# M6_base_simple.net
KiCad netlist of a schematic drawn in Altium Designer
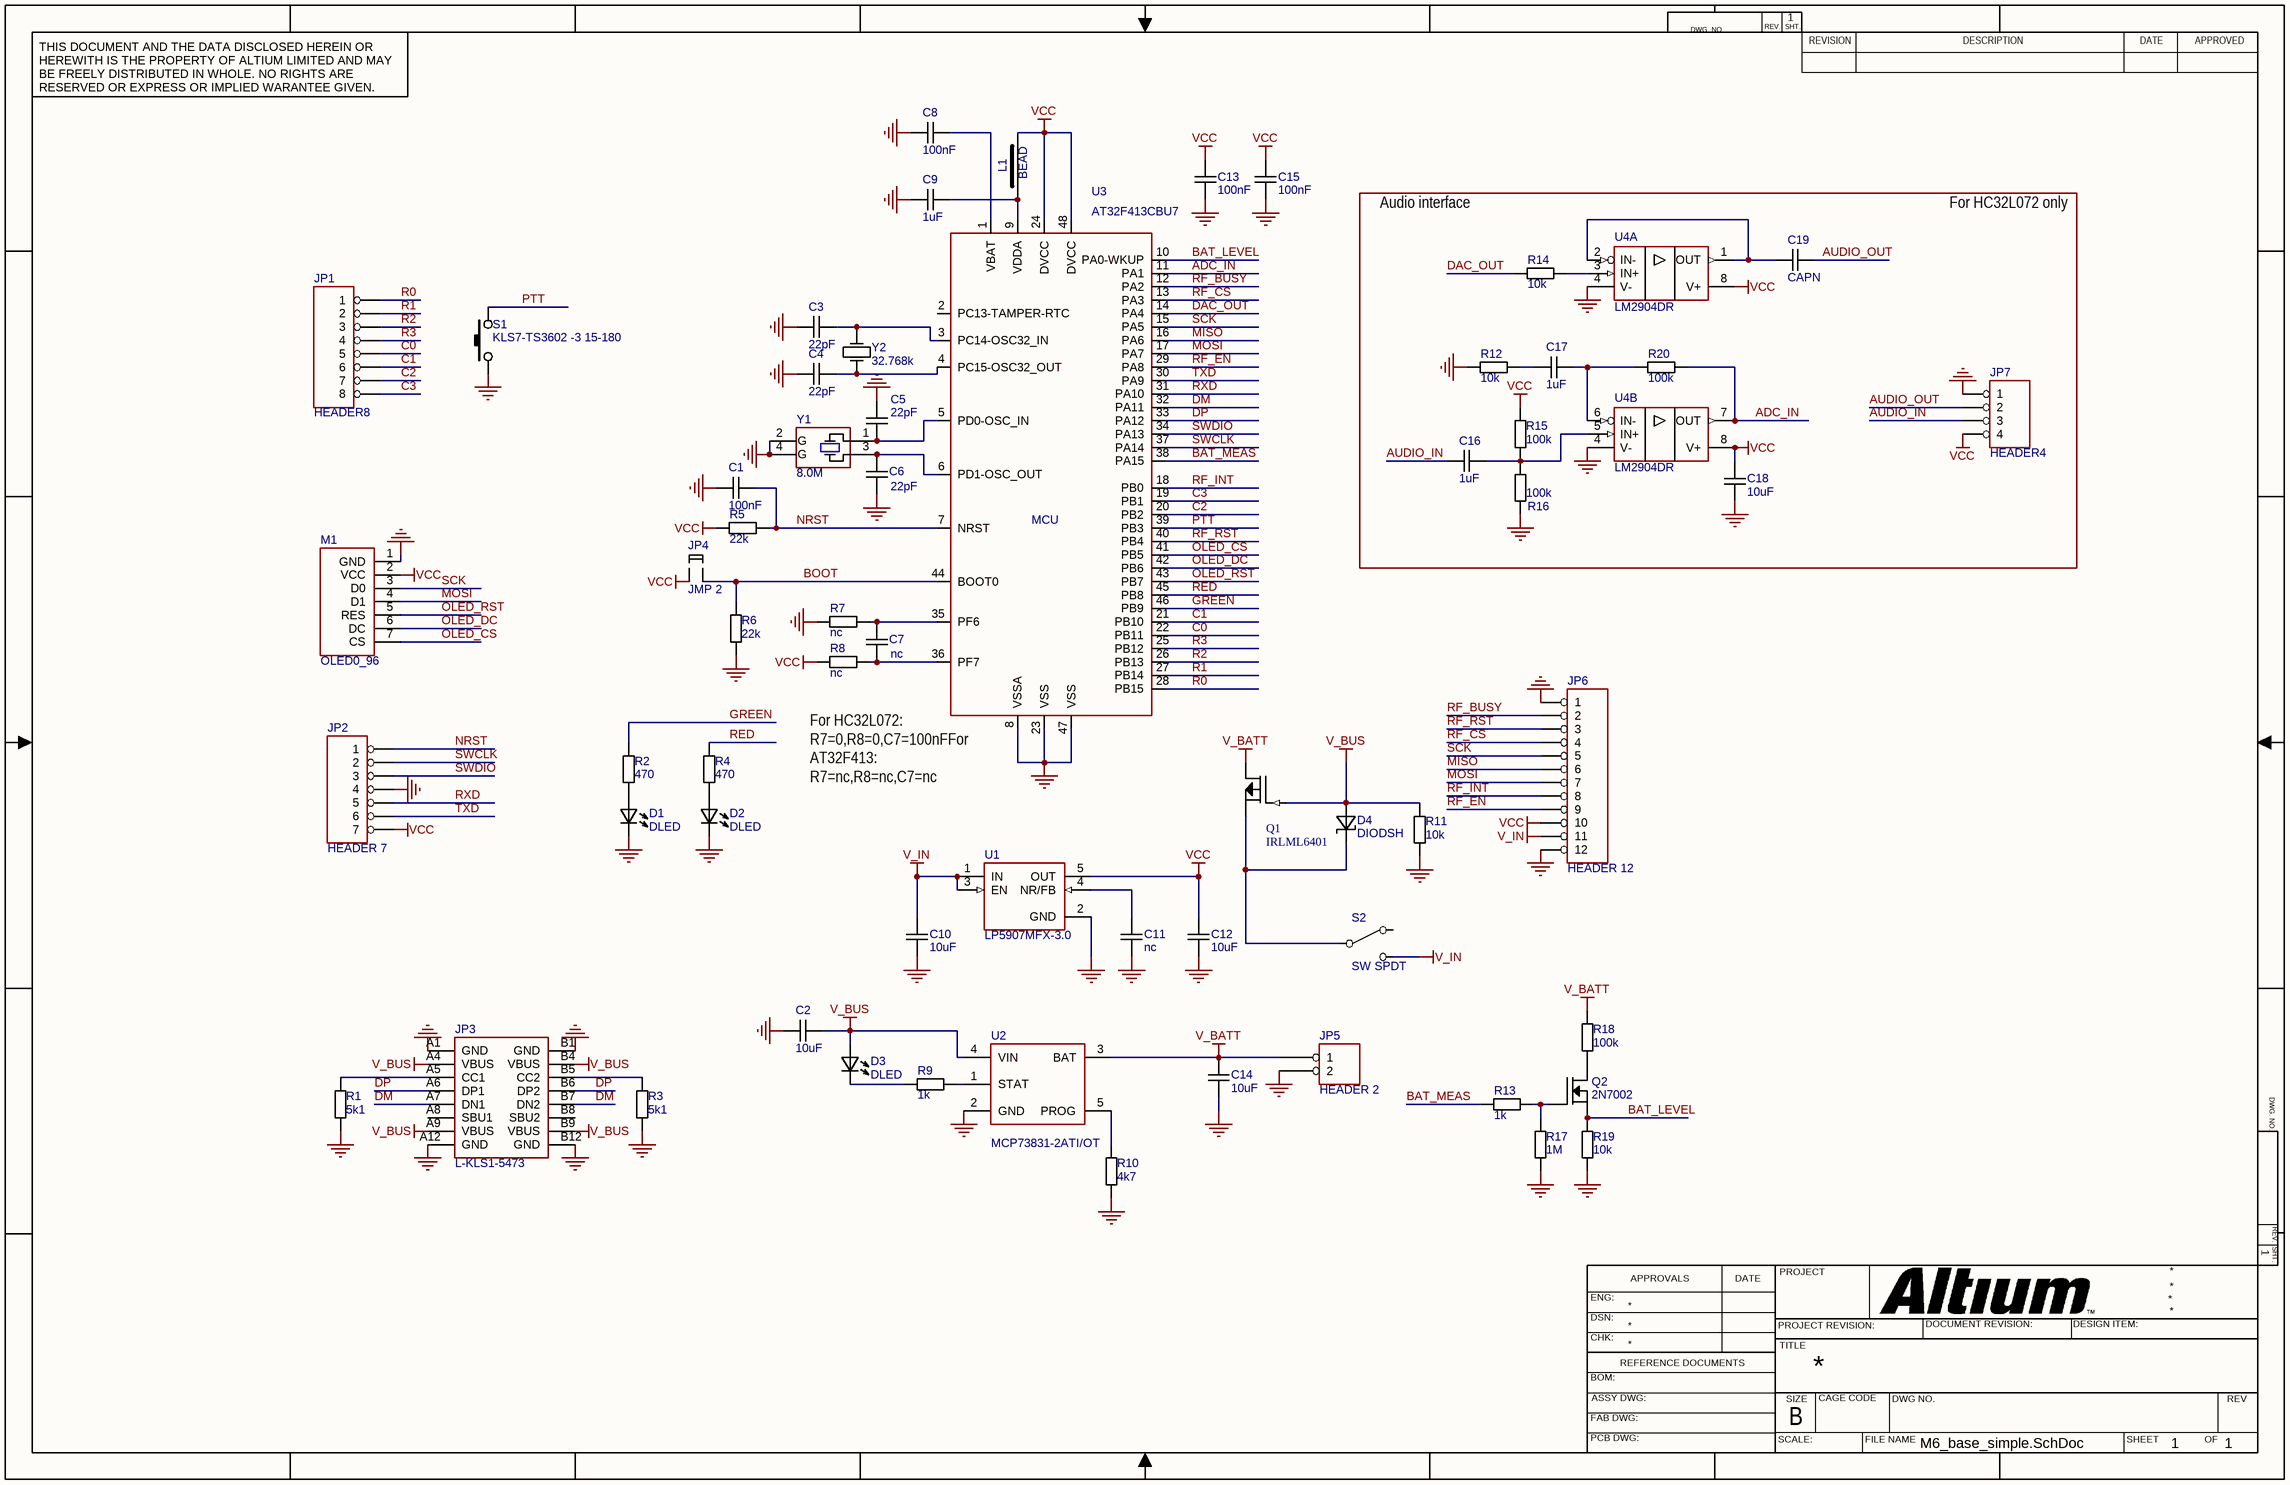
[diagram p0: M6_base_simple.SchDoc]

(export (version "E")
  (design (tool "Eeschema 10.0.6"))
  (components
    (comp (ref "C1")
      (value "100nF")
      (footprint "C-0603")
      (fields (field (name "VOLTAGE") "50V"))
      (libsource (lib "Passive") (part "CAPN"))
    )
    (comp (ref "C2")
      (value "10uF")
      (footprint "C-0805")
      (fields (field (name "VOLTAGE") "50V"))
      (libsource (lib "Passive") (part "CAPN"))
    )
    (comp (ref "C3")
      (value "22pF")
      (footprint "C-0603")
      (fields (field (name "VOLTAGE") "50V"))
      (libsource (lib "Passive") (part "CAPN"))
    )
    (comp (ref "C4")
      (value "22pF")
      (footprint "C-0603")
      (fields (field (name "VOLTAGE") "50V"))
      (libsource (lib "Passive") (part "CAPN"))
    )
    (comp (ref "C5")
      (value "22pF")
      (footprint "C-0603")
      (fields (field (name "VOLTAGE") "50V"))
      (libsource (lib "Passive") (part "CAPN"))
    )
    (comp (ref "C6")
      (value "22pF")
      (footprint "C-0603")
      (fields (field (name "VOLTAGE") "50V"))
      (libsource (lib "Passive") (part "CAPN"))
    )
    (comp (ref "C7")
      (value "nc")
      (footprint "C-0603")
      (fields (field (name "VOLTAGE") "50V"))
      (libsource (lib "Passive") (part "CAPN"))
    )
    (comp (ref "C8")
      (value "100nF")
      (footprint "C-0603")
      (fields (field (name "VOLTAGE") "50V"))
      (libsource (lib "Passive") (part "CAPN"))
    )
    (comp (ref "C9")
      (value "1uF")
      (footprint "C-0603")
      (fields (field (name "VOLTAGE") "50V"))
      (libsource (lib "Passive") (part "CAPN"))
    )
    (comp (ref "C10")
      (value "10uF")
      (footprint "C-0805")
      (fields (field (name "VOLTAGE") "50V"))
      (libsource (lib "Passive") (part "CAPN"))
    )
    (comp (ref "C11")
      (value "nc")
      (footprint "C-0603")
      (fields (field (name "VOLTAGE") "50V"))
      (libsource (lib "Passive") (part "CAPN"))
    )
    (comp (ref "C12")
      (value "10uF")
      (footprint "C-0805")
      (fields (field (name "VOLTAGE") "50V"))
      (libsource (lib "Passive") (part "CAPN"))
    )
    (comp (ref "C13")
      (value "100nF")
      (footprint "C-0603")
      (fields (field (name "VOLTAGE") "50V"))
      (libsource (lib "Passive") (part "CAPN"))
    )
    (comp (ref "C14")
      (value "10uF")
      (footprint "C-0805")
      (fields (field (name "VOLTAGE") "50V"))
      (libsource (lib "Passive") (part "CAPN"))
    )
    (comp (ref "C15")
      (value "100nF")
      (footprint "C-0603")
      (fields (field (name "VOLTAGE") "50V"))
      (libsource (lib "Passive") (part "CAPN"))
    )
    (comp (ref "C16")
      (value "1uF")
      (footprint "C-0603")
      (fields (field (name "VOLTAGE") "50V"))
      (libsource (lib "Passive") (part "CAPN"))
    )
    (comp (ref "C17")
      (value "1uF")
      (footprint "C-0603")
      (fields (field (name "VOLTAGE") "50V"))
      (libsource (lib "Passive") (part "CAPN"))
    )
    (comp (ref "C18")
      (value "10uF")
      (footprint "C-0805")
      (fields (field (name "VOLTAGE") "50V"))
      (libsource (lib "Passive") (part "CAPN"))
    )
    (comp (ref "C19")
      (value "CAPN")
      (footprint "C-0805")
      (fields (field (name "VOLTAGE") "50V"))
      (libsource (lib "Passive") (part "CAPN"))
    )
    (comp (ref "D1") (value "DLED") (footprint "LED_3mm_RED") (libsource (lib "Diodes") (part "DLED")))
    (comp (ref "D2") (value "DLED") (footprint "LED_3mm_RED") (libsource (lib "Diodes") (part "DLED")))
    (comp (ref "D3") (value "DLED") (footprint "LED_3mm_RED") (libsource (lib "Diodes") (part "DLED")))
    (comp (ref "D4") (value "DIODSH") (footprint "D-SMA") (libsource (lib "Diodes") (part "DIODSH")))
    (comp (ref "JP1")
      (value "HEADER8")
      (footprint "PLS1-8R_1")
      (libsource (lib "Connectors") (part "HEADER8"))
    )
    (comp (ref "JP2")
      (value "HEADER 7")
      (footprint "PLS1-7")
      (libsource (lib "Connectors") (part "HEADER 7"))
    )
    (comp (ref "JP3")
      (value "L-KLS1-5473")
      (footprint "L-KLS1-5473")
      (libsource (lib "Connectors") (part "L-KLS1-5473"))
    )
    (comp (ref "JP4") (value "JMP 2") (footprint "PLS1-2") (libsource (lib "Connectors") (part "JMP 2")))
    (comp (ref "JP5")
      (value "HEADER 2")
      (footprint "PLS1-2")
      (libsource (lib "Connectors") (part "HEADER 2"))
    )
    (comp (ref "JP6")
      (value "HEADER 12")
      (footprint "PLS1-12R_1")
      (libsource (lib "Connectors") (part "HEADER 12"))
    )
    (comp (ref "JP7") (value "HEADER4") (footprint "PLS1-4R") (libsource (lib "Connectors") (part "HEADER4")))
    (comp (ref "L1") (value "BEAD") (footprint "L-0603") (libsource (lib "Passive") (part "BEAD")))
    (comp (ref "M1") (value "OLED0_96") (footprint "OLED096") (libsource (lib "RFmodules") (part "OLED0_96")))
    (comp (ref "Q1") (value "IRLML6401") (footprint "SOT-23") (libsource (lib "Discrete") (part "MOSF-P")))
    (comp (ref "Q2") (value "2N7002") (footprint "SOT-23") (libsource (lib "Transistors") (part "MOSF-N")))
    (comp (ref "R1") (value "5k1") (footprint "R-0603") (libsource (lib "Passive") (part "RES")))
    (comp (ref "R2") (value "470") (footprint "R-0603") (libsource (lib "Passive") (part "RES")))
    (comp (ref "R3") (value "5k1") (footprint "R-0603") (libsource (lib "Passive") (part "RES")))
    (comp (ref "R4") (value "470") (footprint "R-0603") (libsource (lib "Passive") (part "RES")))
    (comp (ref "R5") (value "22k") (footprint "R-0603") (libsource (lib "") (part "RES_1")))
    (comp (ref "R6") (value "22k") (footprint "R-0603") (libsource (lib "Passive") (part "RES")))
    (comp (ref "R7") (value "nc") (footprint "R-0603") (libsource (lib "") (part "RES_1")))
    (comp (ref "R8") (value "nc") (footprint "R-0603") (libsource (lib "") (part "RES_1")))
    (comp (ref "R9") (value "1k") (footprint "R-0603") (libsource (lib "") (part "RES_2")))
    (comp (ref "R10") (value "4k7") (footprint "R-0603") (libsource (lib "Passive") (part "RES")))
    (comp (ref "R11") (value "10k") (footprint "R-0603") (libsource (lib "Passive") (part "RES")))
    (comp (ref "R12") (value "10k") (footprint "R-0603") (libsource (lib "") (part "RES_1")))
    (comp (ref "R13") (value "1k") (footprint "R-0603") (libsource (lib "") (part "RES_2")))
    (comp (ref "R14") (value "10k") (footprint "R-0603") (libsource (lib "") (part "RES_1")))
    (comp (ref "R15") (value "100k") (footprint "R-0603") (libsource (lib "Passive") (part "RES")))
    (comp (ref "R16") (value "100k") (footprint "R-0603") (libsource (lib "") (part "RES_3")))
    (comp (ref "R17") (value "1M") (footprint "R-0603") (libsource (lib "Passive") (part "RES")))
    (comp (ref "R18") (value "100k") (footprint "R-0603") (libsource (lib "Passive") (part "RES")))
    (comp (ref "R19") (value "10k") (footprint "R-0603") (libsource (lib "Passive") (part "RES")))
    (comp (ref "R20") (value "100k") (footprint "R-0603") (libsource (lib "") (part "RES_2")))
    (comp (ref "S1")
      (value "KLS7-TS3602 -3 15-180")
      (footprint "KLS7-TS3602")
      (libsource (lib "Switches") (part "SW-1"))
    )
    (comp (ref "S2")
      (value "SW SPDT")
      (footprint "SK-12D07VG5")
      (libsource (lib "Switches") (part "SW SPDT"))
    )
    (comp (ref "U1")
      (value "LP5907MFX-3.0")
      (footprint "SOT-23-5")
      (description "250mA Low-Dropout Regulator")
      (libsource (lib "ICs") (part "LP5907"))
    )
    (comp (ref "U2")
      (value "MCP73831-2ATI/OT")
      (footprint "SOT-23-5")
      (fields
        (field (name "LIBRARY PART") "IC`s.SchLib")
        (field (name "FOOTPRINT PART") "IC-package.PcbLib")
        (field (name "MANUFACTURER") "Texas Instruments")
      )
      (libsource (lib "ICs") (part "MCP73831-2ATI/OT"))
    )
    (comp (ref "U3")
      (value "AT32F413CBU7")
      (footprint "LQFP-48")
      (libsource (lib "MCUs") (part "AT32F413CBU7"))
    )
    (comp (ref "U4")
      (value "LM2904DR")
      (footprint "SO-8")
      (description "Dual Operational Amplifiers, SOIC-8")
      (libsource (lib "ICs") (part "LM2904"))
    )
    (comp (ref "Y1")
      (value "8.0M")
      (footprint "ZQ_SJK-7U")
      (description "Crystal, 24 MHz, 9 pF, SMD")
      (libsource (lib "Passive") (part "TSX-3225"))
    )
    (comp (ref "Y2") (value "32.768k") (footprint "KX-327") (libsource (lib "Passive") (part "Y")))
  )
  (nets
    (net (code "1") (name "/ADC_IN") (class "Default")
      (node (ref "R20") (pin "1") (pinfunction "1_1") (pintype "passive"))
      (node (ref "U3") (pin "11") (pinfunction "PA1_11") (pintype "passive"))
      (node (ref "U4") (pin "7") (pinfunction "OUT_7") (pintype "output"))
    )
    (net (code "2") (name "/AUDIO_IN") (class "Default")
      (node (ref "C16") (pin "1") (pinfunction "1_1") (pintype "passive"))
      (node (ref "JP7") (pin "3") (pinfunction "3_3") (pintype "passive"))
    )
    (net (code "3") (name "/AUDIO_OUT") (class "Default")
      (node (ref "C19") (pin "2") (pinfunction "2_2") (pintype "passive"))
      (node (ref "JP7") (pin "2") (pinfunction "2_2") (pintype "passive"))
    )
    (net (code "4") (name "/BAT_LEVEL") (class "Default")
      (node (ref "Q2") (pin "2") (pinfunction "SOURCE_2") (pintype "passive"))
      (node (ref "R19") (pin "2") (pinfunction "2_2") (pintype "passive"))
      (node (ref "U3") (pin "10") (pinfunction "PA0-WKUP_10") (pintype "passive"))
    )
    (net (code "5") (name "/BAT_MEAS") (class "Default")
      (node (ref "R13") (pin "2") (pinfunction "2_2") (pintype "passive"))
      (node (ref "U3") (pin "38") (pinfunction "PA15_38") (pintype "passive"))
    )
    (net (code "6") (name "/BOOT") (class "Default")
      (node (ref "JP4") (pin "2") (pinfunction "2_2") (pintype "passive"))
      (node (ref "R6") (pin "2") (pinfunction "2_2") (pintype "passive"))
      (node (ref "U3") (pin "44") (pinfunction "BOOT0_44") (pintype "passive"))
    )
    (net (code "7") (name "/C0") (class "Default")
      (node (ref "JP1") (pin "5") (pinfunction "5_5") (pintype "passive"))
      (node (ref "U3") (pin "22") (pinfunction "PB11_22") (pintype "passive"))
    )
    (net (code "8") (name "/C1") (class "Default")
      (node (ref "JP1") (pin "6") (pinfunction "6_6") (pintype "passive"))
      (node (ref "U3") (pin "21") (pinfunction "PB10_21") (pintype "passive"))
    )
    (net (code "9") (name "/C2") (class "Default")
      (node (ref "JP1") (pin "7") (pinfunction "7_7") (pintype "passive"))
      (node (ref "U3") (pin "20") (pinfunction "PB2_20") (pintype "passive"))
    )
    (net (code "10") (name "/C3") (class "Default")
      (node (ref "JP1") (pin "8") (pinfunction "8_8") (pintype "passive"))
      (node (ref "U3") (pin "19") (pinfunction "PB1_19") (pintype "passive"))
    )
    (net (code "11") (name "/DAC_OUT") (class "Default")
      (node (ref "R14") (pin "1") (pinfunction "1_1") (pintype "passive"))
      (node (ref "U3") (pin "14") (pinfunction "PA4_14") (pintype "passive"))
    )
    (net (code "12") (name "/DM") (class "Default")
      (node (ref "JP3") (pin "A7") (pinfunction "DN1_A7") (pintype "passive"))
      (node (ref "JP3") (pin "B7") (pinfunction "DN2_B7") (pintype "passive"))
      (node (ref "U3") (pin "32") (pinfunction "PA11_32") (pintype "passive"))
    )
    (net (code "13") (name "/DP") (class "Default")
      (node (ref "JP3") (pin "A6") (pinfunction "DP1_A6") (pintype "passive"))
      (node (ref "JP3") (pin "B6") (pinfunction "DP2_B6") (pintype "passive"))
      (node (ref "U3") (pin "33") (pinfunction "PA12_33") (pintype "passive"))
    )
    (net (code "14") (name "/GREEN") (class "Default")
      (node (ref "R2") (pin "2") (pinfunction "2_2") (pintype "passive"))
      (node (ref "U3") (pin "46") (pinfunction "PB9_46") (pintype "passive"))
    )
    (net (code "15") (name "/MISO") (class "Default")
      (node (ref "JP6") (pin "6") (pinfunction "6_6") (pintype "passive"))
      (node (ref "U3") (pin "16") (pinfunction "PA6_16") (pintype "passive"))
    )
    (net (code "16") (name "/MOSI") (class "Default")
      (node (ref "JP6") (pin "7") (pinfunction "7_7") (pintype "passive"))
      (node (ref "M1") (pin "4") (pinfunction "D1_4") (pintype "passive"))
      (node (ref "U3") (pin "17") (pinfunction "PA7_17") (pintype "passive"))
    )
    (net (code "17") (name "/NRST") (class "Default")
      (node (ref "C1") (pin "2") (pinfunction "2_2") (pintype "passive"))
      (node (ref "JP2") (pin "1") (pinfunction "1_1") (pintype "passive"))
      (node (ref "R5") (pin "2") (pinfunction "2_2") (pintype "passive"))
      (node (ref "U3") (pin "7") (pinfunction "NRST_7") (pintype "passive"))
    )
    (net (code "18") (name "/OLED_CS") (class "Default")
      (node (ref "M1") (pin "7") (pinfunction "CS_7") (pintype "passive"))
      (node (ref "U3") (pin "41") (pinfunction "PB5_41") (pintype "passive"))
    )
    (net (code "19") (name "/OLED_DC") (class "Default")
      (node (ref "M1") (pin "6") (pinfunction "DC_6") (pintype "passive"))
      (node (ref "U3") (pin "42") (pinfunction "PB6_42") (pintype "passive"))
    )
    (net (code "20") (name "/OLED_RST") (class "Default")
      (node (ref "M1") (pin "5") (pinfunction "RES_5") (pintype "passive"))
      (node (ref "U3") (pin "43") (pinfunction "PB7_43") (pintype "passive"))
    )
    (net (code "21") (name "/PTT") (class "Default")
      (node (ref "S1") (pin "2") (pinfunction "2_2") (pintype "passive"))
      (node (ref "U3") (pin "39") (pinfunction "PB3_39") (pintype "passive"))
    )
    (net (code "22") (name "/R0") (class "Default")
      (node (ref "JP1") (pin "1") (pinfunction "1_1") (pintype "passive"))
      (node (ref "U3") (pin "28") (pinfunction "PB15_28") (pintype "passive"))
    )
    (net (code "23") (name "/R1") (class "Default")
      (node (ref "JP1") (pin "2") (pinfunction "2_2") (pintype "passive"))
      (node (ref "U3") (pin "27") (pinfunction "PB14_27") (pintype "passive"))
    )
    (net (code "24") (name "/R2") (class "Default")
      (node (ref "JP1") (pin "3") (pinfunction "3_3") (pintype "passive"))
      (node (ref "U3") (pin "26") (pinfunction "PB13_26") (pintype "passive"))
    )
    (net (code "25") (name "/R3") (class "Default")
      (node (ref "JP1") (pin "4") (pinfunction "4_4") (pintype "passive"))
      (node (ref "U3") (pin "25") (pinfunction "PB12_25") (pintype "passive"))
    )
    (net (code "26") (name "/RED") (class "Default")
      (node (ref "R4") (pin "2") (pinfunction "2_2") (pintype "passive"))
      (node (ref "U3") (pin "45") (pinfunction "PB8_45") (pintype "passive"))
    )
    (net (code "27") (name "/RF_BUSY") (class "Default")
      (node (ref "JP6") (pin "2") (pinfunction "2_2") (pintype "passive"))
      (node (ref "U3") (pin "12") (pinfunction "PA2_12") (pintype "passive"))
    )
    (net (code "28") (name "/RF_CS") (class "Default")
      (node (ref "JP6") (pin "4") (pinfunction "4_4") (pintype "passive"))
      (node (ref "U3") (pin "13") (pinfunction "PA3_13") (pintype "passive"))
    )
    (net (code "29") (name "/RF_EN") (class "Default")
      (node (ref "JP6") (pin "9") (pinfunction "9_9") (pintype "passive"))
      (node (ref "U3") (pin "29") (pinfunction "PA8_29") (pintype "passive"))
    )
    (net (code "30") (name "/RF_INT") (class "Default")
      (node (ref "JP6") (pin "8") (pinfunction "8_8") (pintype "passive"))
      (node (ref "U3") (pin "18") (pinfunction "PB0_18") (pintype "passive"))
    )
    (net (code "31") (name "/RF_RST") (class "Default")
      (node (ref "JP6") (pin "3") (pinfunction "3_3") (pintype "passive"))
      (node (ref "U3") (pin "40") (pinfunction "PB4_40") (pintype "passive"))
    )
    (net (code "32") (name "/RXD") (class "Default")
      (node (ref "JP2") (pin "5") (pinfunction "5_5") (pintype "passive"))
      (node (ref "U3") (pin "31") (pinfunction "PA10_31") (pintype "passive"))
    )
    (net (code "33") (name "/SCK") (class "Default")
      (node (ref "JP6") (pin "5") (pinfunction "5_5") (pintype "passive"))
      (node (ref "M1") (pin "3") (pinfunction "D0_3") (pintype "passive"))
      (node (ref "U3") (pin "15") (pinfunction "PA5_15") (pintype "passive"))
    )
    (net (code "34") (name "/SWCLK") (class "Default")
      (node (ref "JP2") (pin "2") (pinfunction "2_2") (pintype "passive"))
      (node (ref "U3") (pin "37") (pinfunction "PA14_37") (pintype "passive"))
    )
    (net (code "35") (name "/SWDIO") (class "Default")
      (node (ref "JP2") (pin "3") (pinfunction "3_3") (pintype "passive"))
      (node (ref "U3") (pin "34") (pinfunction "PA13_34") (pintype "passive"))
    )
    (net (code "36") (name "/TXD") (class "Default")
      (node (ref "JP2") (pin "6") (pinfunction "6_6") (pintype "passive"))
      (node (ref "U3") (pin "30") (pinfunction "PA9_30") (pintype "passive"))
    )
    (net (code "37") (name "GND") (class "Default")
      (node (ref "C1") (pin "1") (pinfunction "1_1") (pintype "passive"))
      (node (ref "C10") (pin "2") (pinfunction "2_2") (pintype "passive"))
      (node (ref "C11") (pin "2") (pinfunction "2_2") (pintype "passive"))
      (node (ref "C12") (pin "2") (pinfunction "2_2") (pintype "passive"))
      (node (ref "C13") (pin "1") (pinfunction "1_1") (pintype "passive"))
      (node (ref "C14") (pin "1") (pinfunction "1_1") (pintype "passive"))
      (node (ref "C15") (pin "1") (pinfunction "1_1") (pintype "passive"))
      (node (ref "C18") (pin "1") (pinfunction "1_1") (pintype "passive"))
      (node (ref "C2") (pin "1") (pinfunction "1_1") (pintype "passive"))
      (node (ref "C3") (pin "1") (pinfunction "1_1") (pintype "passive"))
      (node (ref "C4") (pin "1") (pinfunction "1_1") (pintype "passive"))
      (node (ref "C5") (pin "1") (pinfunction "1_1") (pintype "passive"))
      (node (ref "C6") (pin "2") (pinfunction "2_2") (pintype "passive"))
      (node (ref "C8") (pin "2") (pinfunction "2_2") (pintype "passive"))
      (node (ref "C9") (pin "1") (pinfunction "1_1") (pintype "passive"))
      (node (ref "D1") (pin "2") (pinfunction "2_2") (pintype "passive"))
      (node (ref "D2") (pin "2") (pinfunction "2_2") (pintype "passive"))
      (node (ref "JP2") (pin "4") (pinfunction "4_4") (pintype "passive"))
      (node (ref "JP3") (pin "A1") (pinfunction "GND_A1") (pintype "passive"))
      (node (ref "JP3") (pin "A12") (pinfunction "GND_A12") (pintype "passive"))
      (node (ref "JP3") (pin "B1") (pinfunction "GND_B1") (pintype "passive"))
      (node (ref "JP3") (pin "B12") (pinfunction "GND_B12") (pintype "passive"))
      (node (ref "JP5") (pin "2") (pinfunction "2_2") (pintype "passive"))
      (node (ref "JP6") (pin "1") (pinfunction "1_1") (pintype "passive"))
      (node (ref "JP6") (pin "12") (pinfunction "12_12") (pintype "passive"))
      (node (ref "JP7") (pin "1") (pinfunction "1_1") (pintype "passive"))
      (node (ref "M1") (pin "1") (pinfunction "GND_1") (pintype "passive"))
      (node (ref "R1") (pin "1") (pinfunction "1_1") (pintype "passive"))
      (node (ref "R10") (pin "1") (pinfunction "1_1") (pintype "passive"))
      (node (ref "R11") (pin "1") (pinfunction "1_1") (pintype "passive"))
      (node (ref "R12") (pin "1") (pinfunction "1_1") (pintype "passive"))
      (node (ref "R16") (pin "2") (pinfunction "2_2") (pintype "passive"))
      (node (ref "R17") (pin "1") (pinfunction "1_1") (pintype "passive"))
      (node (ref "R19") (pin "1") (pinfunction "1_1") (pintype "passive"))
      (node (ref "R3") (pin "1") (pinfunction "1_1") (pintype "passive"))
      (node (ref "R6") (pin "1") (pinfunction "1_1") (pintype "passive"))
      (node (ref "R7") (pin "1") (pinfunction "1_1") (pintype "passive"))
      (node (ref "S1") (pin "1") (pinfunction "1_1") (pintype "passive"))
      (node (ref "U1") (pin "2") (pinfunction "GND_2") (pintype "power_in"))
      (node (ref "U2") (pin "2") (pinfunction "GND_2") (pintype "passive"))
      (node (ref "U3") (pin "23") (pinfunction "VSS_23") (pintype "passive"))
      (node (ref "U3") (pin "47") (pinfunction "VSS_47") (pintype "passive"))
      (node (ref "U3") (pin "8") (pinfunction "VSSA_8") (pintype "passive"))
      (node (ref "U4") (pin "4") (pinfunction "V-_4") (pintype "power_in"))
      (node (ref "Y1") (pin "2") (pinfunction "GND_2") (pintype "power_in"))
      (node (ref "Y1") (pin "4") (pinfunction "GND_4") (pintype "power_in"))
    )
    (net (code "38") (name "Net-(C17-Pad1)") (class "Default")
      (node (ref "C17") (pin "1") (pinfunction "1_1") (pintype "passive"))
      (node (ref "R12") (pin "2") (pinfunction "2_2") (pintype "passive"))
    )
    (net (code "39") (name "Net-(D1-Pad1)") (class "Default")
      (node (ref "D1") (pin "1") (pinfunction "1_1") (pintype "passive"))
      (node (ref "R2") (pin "1") (pinfunction "1_1") (pintype "passive"))
    )
    (net (code "40") (name "Net-(D2-Pad1)") (class "Default")
      (node (ref "D2") (pin "1") (pinfunction "1_1") (pintype "passive"))
      (node (ref "R4") (pin "1") (pinfunction "1_1") (pintype "passive"))
    )
    (net (code "41") (name "Net-(D3-Pad2)") (class "Default")
      (node (ref "D3") (pin "2") (pinfunction "2_2") (pintype "passive"))
      (node (ref "R9") (pin "2") (pinfunction "2_2") (pintype "passive"))
    )
    (net (code "42") (name "Net-(JP3-CC1)") (class "Default")
      (node (ref "JP3") (pin "A5") (pinfunction "CC1_A5") (pintype "passive"))
      (node (ref "R1") (pin "2") (pinfunction "2_2") (pintype "passive"))
    )
    (net (code "43") (name "Net-(JP3-CC2)") (class "Default")
      (node (ref "JP3") (pin "B5") (pinfunction "CC2_B5") (pintype "passive"))
      (node (ref "R3") (pin "2") (pinfunction "2_2") (pintype "passive"))
    )
    (net (code "44") (name "Net-(Q1-SOURCE)") (class "Default")
      (node (ref "D4") (pin "2") (pinfunction "2_2") (pintype "passive"))
      (node (ref "Q1") (pin "2") (pinfunction "SOURCE_2") (pintype "passive"))
      (node (ref "S2") (pin "2") (pinfunction "COMMON_2") (pintype "passive"))
    )
    (net (code "45") (name "Net-(Q2-DRAIN)") (class "Default")
      (node (ref "Q2") (pin "3") (pinfunction "DRAIN_3") (pintype "passive"))
      (node (ref "R18") (pin "1") (pinfunction "1_1") (pintype "passive"))
    )
    (net (code "46") (name "Net-(Q2-GATE)") (class "Default")
      (node (ref "Q2") (pin "1") (pinfunction "GATE_1") (pintype "passive"))
      (node (ref "R13") (pin "1") (pinfunction "1_1") (pintype "passive"))
      (node (ref "R17") (pin "2") (pinfunction "2_2") (pintype "passive"))
    )
    (net (code "47") (name "Net-(U1-NR{slash}FB)") (class "Default")
      (node (ref "C11") (pin "1") (pinfunction "1_1") (pintype "passive"))
      (node (ref "U1") (pin "4") (pinfunction "NR/FB_4") (pintype "input"))
    )
    (net (code "48") (name "Net-(U2-PROG)") (class "Default")
      (node (ref "R10") (pin "2") (pinfunction "2_2") (pintype "passive"))
      (node (ref "U2") (pin "5") (pinfunction "PROG_5") (pintype "passive"))
    )
    (net (code "49") (name "Net-(U2-STAT)") (class "Default")
      (node (ref "R9") (pin "1") (pinfunction "1_1") (pintype "passive"))
      (node (ref "U2") (pin "1") (pinfunction "STAT_1") (pintype "passive"))
    )
    (net (code "50") (name "Net-(U3-PC14-OSC32_IN)") (class "Default")
      (node (ref "C3") (pin "2") (pinfunction "2_2") (pintype "passive"))
      (node (ref "U3") (pin "3") (pinfunction "PC14-OSC32_IN_3") (pintype "passive"))
      (node (ref "Y2") (pin "2") (pinfunction "2_2") (pintype "passive"))
    )
    (net (code "51") (name "Net-(U3-PC15-OSC32_OUT)") (class "Default")
      (node (ref "C4") (pin "2") (pinfunction "2_2") (pintype "passive"))
      (node (ref "U3") (pin "4") (pinfunction "PC15-OSC32_OUT_4") (pintype "passive"))
      (node (ref "Y2") (pin "1") (pinfunction "1_1") (pintype "passive"))
    )
    (net (code "52") (name "Net-(U3-PD0-OSC_IN)") (class "Default")
      (node (ref "C5") (pin "2") (pinfunction "2_2") (pintype "passive"))
      (node (ref "U3") (pin "5") (pinfunction "PD0-OSC_IN_5") (pintype "passive"))
      (node (ref "Y1") (pin "1") (pinfunction "1_1") (pintype "passive"))
    )
    (net (code "53") (name "Net-(U3-PD1-OSC_OUT)") (class "Default")
      (node (ref "C6") (pin "1") (pinfunction "1_1") (pintype "passive"))
      (node (ref "U3") (pin "6") (pinfunction "PD1-OSC_OUT_6") (pintype "passive"))
      (node (ref "Y1") (pin "3") (pinfunction "3_3") (pintype "passive"))
    )
    (net (code "54") (name "Net-(U3-PF6)") (class "Default")
      (node (ref "C7") (pin "1") (pinfunction "1_1") (pintype "passive"))
      (node (ref "R7") (pin "2") (pinfunction "2_2") (pintype "passive"))
      (node (ref "U3") (pin "35") (pinfunction "PF6_35") (pintype "passive"))
    )
    (net (code "55") (name "Net-(U3-PF7)") (class "Default")
      (node (ref "C7") (pin "2") (pinfunction "2_2") (pintype "passive"))
      (node (ref "R8") (pin "2") (pinfunction "2_2") (pintype "passive"))
      (node (ref "U3") (pin "36") (pinfunction "PF7_36") (pintype "passive"))
    )
    (net (code "56") (name "Net-(U3-VBAT)") (class "Default")
      (node (ref "C8") (pin "1") (pinfunction "1_1") (pintype "passive"))
      (node (ref "U3") (pin "1") (pinfunction "VBAT_1") (pintype "passive"))
    )
    (net (code "57") (name "Net-(U3-VDDA)") (class "Default")
      (node (ref "C9") (pin "2") (pinfunction "2_2") (pintype "passive"))
      (node (ref "L1") (pin "1") (pinfunction "1_1") (pintype "passive"))
      (node (ref "U3") (pin "9") (pinfunction "VDDA_9") (pintype "passive"))
    )
    (net (code "58") (name "Net-(U4A-IN+)") (class "Default")
      (node (ref "R14") (pin "2") (pinfunction "2_2") (pintype "passive"))
      (node (ref "U4") (pin "3") (pinfunction "IN+_3") (pintype "input"))
    )
    (net (code "59") (name "Net-(U4A-IN-)") (class "Default")
      (node (ref "C19") (pin "1") (pinfunction "1_1") (pintype "passive"))
      (node (ref "U4") (pin "1") (pinfunction "OUT_1") (pintype "output"))
      (node (ref "U4") (pin "2") (pinfunction "IN-_2") (pintype "input"))
    )
    (net (code "60") (name "Net-(U4B-IN+)") (class "Default")
      (node (ref "C16") (pin "2") (pinfunction "2_2") (pintype "passive"))
      (node (ref "R15") (pin "1") (pinfunction "1_1") (pintype "passive"))
      (node (ref "R16") (pin "1") (pinfunction "1_1") (pintype "passive"))
      (node (ref "U4") (pin "5") (pinfunction "IN+_5") (pintype "input"))
    )
    (net (code "61") (name "Net-(U4B-IN-)") (class "Default")
      (node (ref "C17") (pin "2") (pinfunction "2_2") (pintype "passive"))
      (node (ref "R20") (pin "2") (pinfunction "2_2") (pintype "passive"))
      (node (ref "U4") (pin "6") (pinfunction "IN-_6") (pintype "input"))
    )
    (net (code "62") (name "VCC") (class "Default")
      (node (ref "C12") (pin "1") (pinfunction "1_1") (pintype "passive"))
      (node (ref "C13") (pin "2") (pinfunction "2_2") (pintype "passive"))
      (node (ref "C15") (pin "2") (pinfunction "2_2") (pintype "passive"))
      (node (ref "C18") (pin "2") (pinfunction "2_2") (pintype "passive"))
      (node (ref "JP2") (pin "7") (pinfunction "7_7") (pintype "passive"))
      (node (ref "JP4") (pin "1") (pinfunction "1_1") (pintype "passive"))
      (node (ref "JP6") (pin "10") (pinfunction "10_10") (pintype "passive"))
      (node (ref "JP7") (pin "4") (pinfunction "4_4") (pintype "passive"))
      (node (ref "L1") (pin "2") (pinfunction "2_2") (pintype "passive"))
      (node (ref "M1") (pin "2") (pinfunction "VCC_2") (pintype "passive"))
      (node (ref "R15") (pin "2") (pinfunction "2_2") (pintype "passive"))
      (node (ref "R5") (pin "1") (pinfunction "1_1") (pintype "passive"))
      (node (ref "R8") (pin "1") (pinfunction "1_1") (pintype "passive"))
      (node (ref "U1") (pin "5") (pinfunction "OUT_5") (pintype "power_in"))
      (node (ref "U3") (pin "24") (pinfunction "DVCC_24") (pintype "passive"))
      (node (ref "U3") (pin "48") (pinfunction "DVCC_48") (pintype "passive"))
      (node (ref "U4") (pin "8") (pinfunction "V+_8") (pintype "power_in"))
    )
    (net (code "63") (name "VSS") (class "Default")
      (node (ref "JP3") (pin "17") (pinfunction "VSS_17") (pintype "power_in"))
    )
    (net (code "64") (name "V_BATT") (class "Default")
      (node (ref "C14") (pin "2") (pinfunction "2_2") (pintype "passive"))
      (node (ref "JP5") (pin "1") (pinfunction "1_1") (pintype "passive"))
      (node (ref "Q1") (pin "3") (pinfunction "DRAIN_3") (pintype "passive"))
      (node (ref "R18") (pin "2") (pinfunction "2_2") (pintype "passive"))
      (node (ref "U2") (pin "3") (pinfunction "BAT_3") (pintype "passive"))
    )
    (net (code "65") (name "V_BUS") (class "Default")
      (node (ref "C2") (pin "2") (pinfunction "2_2") (pintype "passive"))
      (node (ref "D3") (pin "1") (pinfunction "1_1") (pintype "passive"))
      (node (ref "D4") (pin "1") (pinfunction "1_1") (pintype "passive"))
      (node (ref "JP3") (pin "A4") (pinfunction "VBUS_A4") (pintype "passive"))
      (node (ref "JP3") (pin "A9") (pinfunction "VBUS_A9") (pintype "passive"))
      (node (ref "JP3") (pin "B4") (pinfunction "VBUS_B4") (pintype "passive"))
      (node (ref "JP3") (pin "B9") (pinfunction "VBUS_B9") (pintype "passive"))
      (node (ref "Q1") (pin "1") (pinfunction "GATE_1") (pintype "input"))
      (node (ref "R11") (pin "2") (pinfunction "2_2") (pintype "passive"))
      (node (ref "U2") (pin "4") (pinfunction "VIN_4") (pintype "passive"))
    )
    (net (code "66") (name "V_IN") (class "Default")
      (node (ref "C10") (pin "1") (pinfunction "1_1") (pintype "passive"))
      (node (ref "JP6") (pin "11") (pinfunction "11_11") (pintype "passive"))
      (node (ref "S2") (pin "3") (pinfunction "NO_3") (pintype "passive"))
      (node (ref "U1") (pin "1") (pinfunction "IN_1") (pintype "power_in"))
      (node (ref "U1") (pin "3") (pinfunction "EN_3") (pintype "input"))
    )
    (net (code "67") (name "unconnected-(JP3-SBU1-PadA8)") (class "Default")
      (node (ref "JP3") (pin "A8") (pinfunction "SBU1_A8") (pintype "passive"))
    )
    (net (code "68") (name "unconnected-(JP3-SBU2-PadB8)") (class "Default")
      (node (ref "JP3") (pin "B8") (pinfunction "SBU2_B8") (pintype "passive"))
    )
    (net (code "69") (name "unconnected-(S2-NC-Pad1)") (class "Default")
      (node (ref "S2") (pin "1") (pinfunction "NC_1") (pintype "passive"))
    )
    (net (code "70") (name "unconnected-(U3-PC13-TAMPER-RTC-Pad2)") (class "Default")
      (node (ref "U3") (pin "2") (pinfunction "PC13-TAMPER-RTC_2") (pintype "passive"))
    )
  )
)
